# schematic.net
KiCad netlist of a schematic drawn in EasyEDA
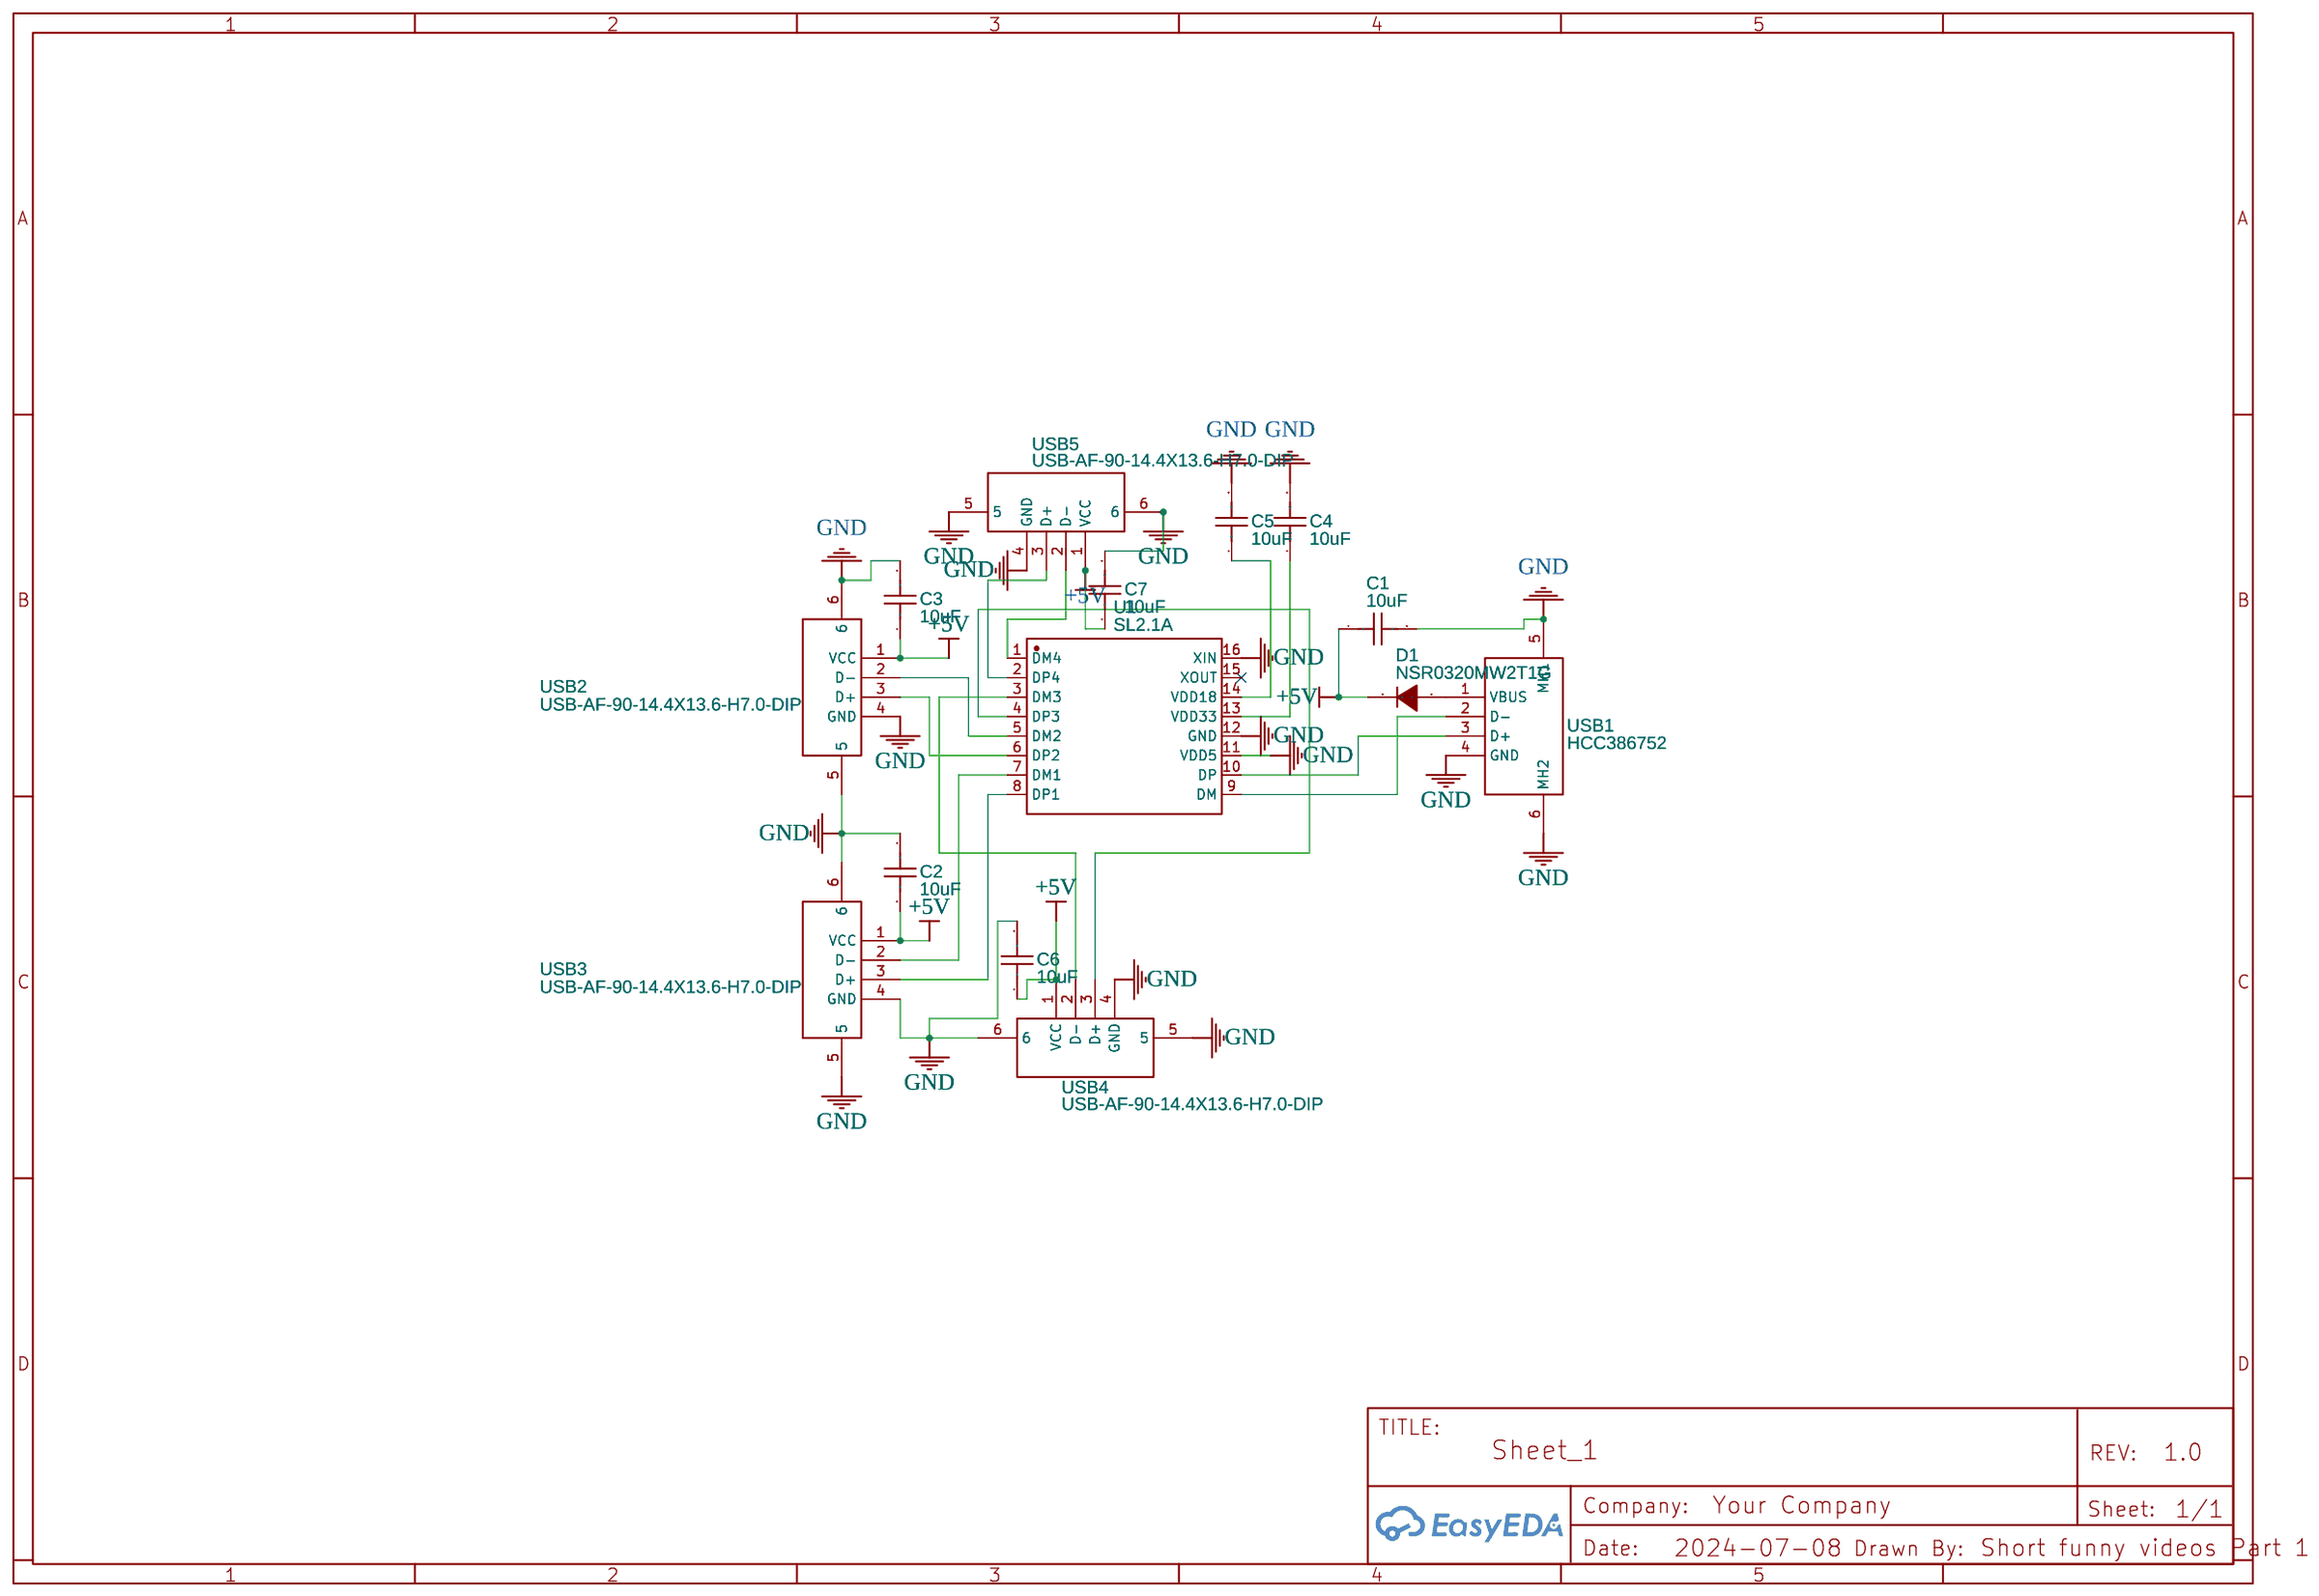
[diagram p0: schematic sheet]

(export (version "E")
  (design (tool "Eeschema 10.0.6"))
  (components
    (comp (ref "C1")
      (value "10uF")
      (fields
        (field (name "Manufacturer Part") "CL10A106KP8NNNC")
        (field (name "Manufacturer") "SAMSUNG(三星)")
      )
      (libsource (lib "") (part "CL10A106KP8NNNC_1"))
    )
    (comp (ref "C2")
      (value "10uF")
      (fields
        (field (name "Manufacturer Part") "CL10A106KP8NNNC")
        (field (name "Manufacturer") "SAMSUNG(三星)")
      )
      (libsource (lib "") (part "CL10A106KP8NNNC_2"))
    )
    (comp (ref "C3")
      (value "10uF")
      (fields
        (field (name "Manufacturer Part") "CL10A106KP8NNNC")
        (field (name "Manufacturer") "SAMSUNG(三星)")
      )
      (libsource (lib "") (part "CL10A106KP8NNNC"))
    )
    (comp (ref "C4")
      (value "10uF")
      (fields
        (field (name "Manufacturer Part") "CL10A106KP8NNNC")
        (field (name "Manufacturer") "SAMSUNG(三星)")
      )
      (libsource (lib "") (part "CL10A106KP8NNNC"))
    )
    (comp (ref "C5")
      (value "10uF")
      (fields
        (field (name "Manufacturer Part") "CL10A106KP8NNNC")
        (field (name "Manufacturer") "SAMSUNG(三星)")
      )
      (libsource (lib "") (part "CL10A106KP8NNNC"))
    )
    (comp (ref "C6")
      (value "10uF")
      (fields
        (field (name "Manufacturer Part") "CL10A106KP8NNNC")
        (field (name "Manufacturer") "SAMSUNG(三星)")
      )
      (libsource (lib "") (part "CL10A106KP8NNNC"))
    )
    (comp (ref "C7")
      (value "10uF")
      (fields
        (field (name "Manufacturer Part") "CL10A106KP8NNNC")
        (field (name "Manufacturer") "SAMSUNG(三星)")
      )
      (libsource (lib "") (part "CL10A106KP8NNNC"))
    )
    (comp (ref "D1")
      (value "NSR0320MW2T1G")
      (fields (field (name "Manufacturer") "onsemi(安森美)"))
      (libsource (lib "") (part "NSR0320MW2T1G"))
    )
    (comp (ref "U1")
      (value "SL2.1A")
      (fields (field (name "Manufacturer") "CoreChips(和芯润德)"))
      (libsource (lib "") (part "SL2.1A"))
    )
    (comp (ref "USB1")
      (value "HCC386752")
      (fields (field (name "Manufacturer Part") "U-USBAR04P-M003") (field (name "Manufacturer") "Ckmtw(灿科盟)"))
      (libsource (lib "") (part "HCC386752"))
    )
    (comp (ref "USB2")
      (value "USB-AF-90-14.4X13.6-H7.0-DIP")
      (fields (field (name "Manufacturer Part") "903-131A1011D10100") (field (name "Manufacturer") "精拓金"))
      (libsource (lib "") (part "USB-AF-90-14.4X13.6-H7.0-DIP_1"))
    )
    (comp (ref "USB3")
      (value "USB-AF-90-14.4X13.6-H7.0-DIP")
      (fields (field (name "Manufacturer Part") "903-131A1011D10100") (field (name "Manufacturer") "精拓金"))
      (libsource (lib "") (part "USB-AF-90-14.4X13.6-H7.0-DIP_1"))
    )
    (comp (ref "USB4")
      (value "USB-AF-90-14.4X13.6-H7.0-DIP")
      (fields (field (name "Manufacturer Part") "903-131A1011D10100") (field (name "Manufacturer") "精拓金"))
      (libsource (lib "") (part "USB-AF-90-14.4X13.6-H7.0-DIP"))
    )
    (comp (ref "USB5")
      (value "USB-AF-90-14.4X13.6-H7.0-DIP")
      (fields (field (name "Manufacturer Part") "903-131A1011D10100") (field (name "Manufacturer") "精拓金"))
      (libsource (lib "") (part "USB-AF-90-14.4X13.6-H7.0-DIP_2"))
    )
  )
  (nets
    (net (code "1") (name "+5V") (class "Default")
      (node (ref "C1") (pin "1") (pinfunction "1_1") (pintype "unspecified"))
      (node (ref "C2") (pin "2") (pinfunction "2_2") (pintype "unspecified"))
      (node (ref "C3") (pin "1") (pinfunction "1_1") (pintype "unspecified"))
      (node (ref "C6") (pin "1") (pinfunction "1_1") (pintype "unspecified"))
      (node (ref "C7") (pin "1") (pinfunction "1_1") (pintype "unspecified"))
      (node (ref "D1") (pin "1") (pinfunction "C_1") (pintype "unspecified"))
      (node (ref "USB2") (pin "1") (pinfunction "VCC_1") (pintype "unspecified"))
      (node (ref "USB3") (pin "1") (pinfunction "VCC_1") (pintype "unspecified"))
      (node (ref "USB4") (pin "1") (pinfunction "VCC_1") (pintype "unspecified"))
      (node (ref "USB5") (pin "1") (pinfunction "VCC_1") (pintype "unspecified"))
    )
    (net (code "2") (name "GND") (class "Default")
      (node (ref "C1") (pin "2") (pinfunction "2_2") (pintype "unspecified"))
      (node (ref "C2") (pin "1") (pinfunction "1_1") (pintype "unspecified"))
      (node (ref "C3") (pin "2") (pinfunction "2_2") (pintype "unspecified"))
      (node (ref "C4") (pin "2") (pinfunction "2_2") (pintype "unspecified"))
      (node (ref "C5") (pin "2") (pinfunction "2_2") (pintype "unspecified"))
      (node (ref "C6") (pin "2") (pinfunction "2_2") (pintype "unspecified"))
      (node (ref "C7") (pin "2") (pinfunction "2_2") (pintype "unspecified"))
      (node (ref "U1") (pin "11") (pinfunction "VDD5_11") (pintype "unspecified"))
      (node (ref "U1") (pin "12") (pinfunction "GND_12") (pintype "unspecified"))
      (node (ref "U1") (pin "16") (pinfunction "XIN_16") (pintype "unspecified"))
      (node (ref "USB1") (pin "4") (pinfunction "GND_4") (pintype "unspecified"))
      (node (ref "USB1") (pin "5") (pinfunction "MH1_5") (pintype "unspecified"))
      (node (ref "USB1") (pin "6") (pinfunction "MH2_6") (pintype "unspecified"))
      (node (ref "USB2") (pin "4") (pinfunction "GND_4") (pintype "unspecified"))
      (node (ref "USB2") (pin "5") (pinfunction "5_5") (pintype "unspecified"))
      (node (ref "USB2") (pin "6") (pinfunction "6_6") (pintype "unspecified"))
      (node (ref "USB3") (pin "4") (pinfunction "GND_4") (pintype "unspecified"))
      (node (ref "USB3") (pin "5") (pinfunction "5_5") (pintype "unspecified"))
      (node (ref "USB3") (pin "6") (pinfunction "6_6") (pintype "unspecified"))
      (node (ref "USB4") (pin "4") (pinfunction "GND_4") (pintype "unspecified"))
      (node (ref "USB4") (pin "5") (pinfunction "5_5") (pintype "unspecified"))
      (node (ref "USB4") (pin "6") (pinfunction "6_6") (pintype "unspecified"))
      (node (ref "USB5") (pin "4") (pinfunction "GND_4") (pintype "unspecified"))
      (node (ref "USB5") (pin "5") (pinfunction "5_5") (pintype "unspecified"))
      (node (ref "USB5") (pin "6") (pinfunction "6_6") (pintype "unspecified"))
    )
    (net (code "3") (name "Net-(D1-A)") (class "Default")
      (node (ref "D1") (pin "2") (pinfunction "A_2") (pintype "unspecified"))
      (node (ref "USB1") (pin "1") (pinfunction "VBUS_1") (pintype "unspecified"))
    )
    (net (code "4") (name "Net-(U1-DM)") (class "Default")
      (node (ref "U1") (pin "9") (pinfunction "DM_9") (pintype "unspecified"))
      (node (ref "USB1") (pin "2") (pinfunction "D-_2") (pintype "unspecified"))
    )
    (net (code "5") (name "Net-(U1-DM1)") (class "Default")
      (node (ref "U1") (pin "7") (pinfunction "DM1_7") (pintype "unspecified"))
      (node (ref "USB3") (pin "2") (pinfunction "D-_2") (pintype "unspecified"))
    )
    (net (code "6") (name "Net-(U1-DM2)") (class "Default")
      (node (ref "U1") (pin "5") (pinfunction "DM2_5") (pintype "unspecified"))
      (node (ref "USB2") (pin "2") (pinfunction "D-_2") (pintype "unspecified"))
    )
    (net (code "7") (name "Net-(U1-DM3)") (class "Default")
      (node (ref "U1") (pin "3") (pinfunction "DM3_3") (pintype "unspecified"))
      (node (ref "USB4") (pin "2") (pinfunction "D-_2") (pintype "unspecified"))
    )
    (net (code "8") (name "Net-(U1-DM4)") (class "Default")
      (node (ref "U1") (pin "1") (pinfunction "DM4_1") (pintype "unspecified"))
      (node (ref "USB5") (pin "2") (pinfunction "D-_2") (pintype "unspecified"))
    )
    (net (code "9") (name "Net-(U1-DP)") (class "Default")
      (node (ref "U1") (pin "10") (pinfunction "DP_10") (pintype "unspecified"))
      (node (ref "USB1") (pin "3") (pinfunction "D+_3") (pintype "unspecified"))
    )
    (net (code "10") (name "Net-(U1-DP1)") (class "Default")
      (node (ref "U1") (pin "8") (pinfunction "DP1_8") (pintype "unspecified"))
      (node (ref "USB3") (pin "3") (pinfunction "D+_3") (pintype "unspecified"))
    )
    (net (code "11") (name "Net-(U1-DP2)") (class "Default")
      (node (ref "U1") (pin "6") (pinfunction "DP2_6") (pintype "unspecified"))
      (node (ref "USB2") (pin "3") (pinfunction "D+_3") (pintype "unspecified"))
    )
    (net (code "12") (name "Net-(U1-DP3)") (class "Default")
      (node (ref "U1") (pin "4") (pinfunction "DP3_4") (pintype "unspecified"))
      (node (ref "USB4") (pin "3") (pinfunction "D+_3") (pintype "unspecified"))
    )
    (net (code "13") (name "Net-(U1-DP4)") (class "Default")
      (node (ref "U1") (pin "2") (pinfunction "DP4_2") (pintype "unspecified"))
      (node (ref "USB5") (pin "3") (pinfunction "D+_3") (pintype "unspecified"))
    )
    (net (code "14") (name "Net-(U1-VDD18)") (class "Default")
      (node (ref "C5") (pin "1") (pinfunction "1_1") (pintype "unspecified"))
      (node (ref "U1") (pin "14") (pinfunction "VDD18_14") (pintype "unspecified"))
    )
    (net (code "15") (name "Net-(U1-VDD33)") (class "Default")
      (node (ref "C4") (pin "1") (pinfunction "1_1") (pintype "unspecified"))
      (node (ref "U1") (pin "13") (pinfunction "VDD33_13") (pintype "unspecified"))
    )
    (net (code "16") (name "unconnected-(U1-XOUT-Pad15)") (class "Default")
      (node (ref "U1") (pin "15") (pinfunction "XOUT_15") (pintype "unspecified+no_connect"))
    )
  )
)
